# XM5062_33.net
KiCad netlist of a schematic drawn in Altium Designer
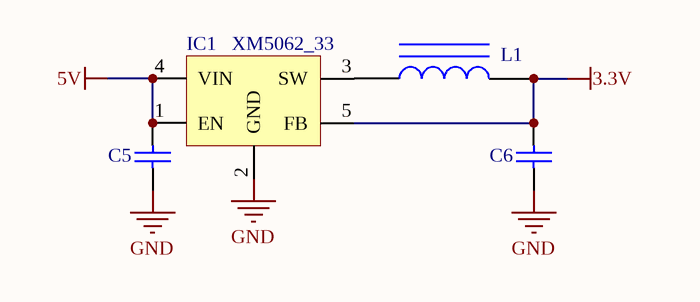
[diagram p0: XM5062_33.SchDoc]

(export (version "E")
  (design (tool "Eeschema 10.0.6"))
  (components
    (comp (ref "C5")
      (value "4.7uF")
      (footprint "CAP-0603")
      (description "贴片电容")
      (libsource (lib "Power_Lib_Altium") (part "CAP"))
    )
    (comp (ref "C6")
      (value "10uF")
      (footprint "CAP-0603")
      (description "贴片电容")
      (libsource (lib "Power_Lib_Altium") (part "CAP"))
    )
    (comp (ref "IC1")
      (value "XM5062_33")
      (footprint "SOT-23-5")
      (description "降压转换芯片")
      (fields (field (name "MANUFACTURER_PART_NUMBER") "1-1393258-5"))
      (libsource (lib "Power_Lib_Altium") (part "XM5062"))
    )
    (comp (ref "L1")
      (value "2.2uH")
      (footprint "XAL6060-103MEB")
      (description "贴片电感")
      (libsource (lib "Power_Lib_Altium") (part "INDUCTOR"))
    )
  )
  (nets
    (net (code "1") (name "3.3V") (class "Default")
      (node (ref "C6") (pin "2") (pinfunction "2_2") (pintype "passive"))
      (node (ref "IC1") (pin "5") (pinfunction "FB_5") (pintype "passive"))
      (node (ref "L1") (pin "2") (pinfunction "2_2") (pintype "passive"))
    )
    (net (code "2") (name "5V") (class "Default")
      (node (ref "C5") (pin "2") (pinfunction "2_2") (pintype "passive"))
      (node (ref "IC1") (pin "1") (pinfunction "EN_1") (pintype "passive"))
      (node (ref "IC1") (pin "4") (pinfunction "VIN_4") (pintype "passive"))
    )
    (net (code "3") (name "GND") (class "Default")
      (node (ref "C5") (pin "1") (pinfunction "1_1") (pintype "passive"))
      (node (ref "C6") (pin "1") (pinfunction "1_1") (pintype "passive"))
      (node (ref "IC1") (pin "2") (pinfunction "GND_2") (pintype "passive"))
    )
    (net (code "4") (name "Net-(IC1-SW)") (class "Default")
      (node (ref "IC1") (pin "3") (pinfunction "SW_3") (pintype "passive"))
      (node (ref "L1") (pin "1") (pinfunction "1_1") (pintype "passive"))
    )
  )
)
